# injectors.net
KiCad netlist of a schematic drawn in Altium Designer
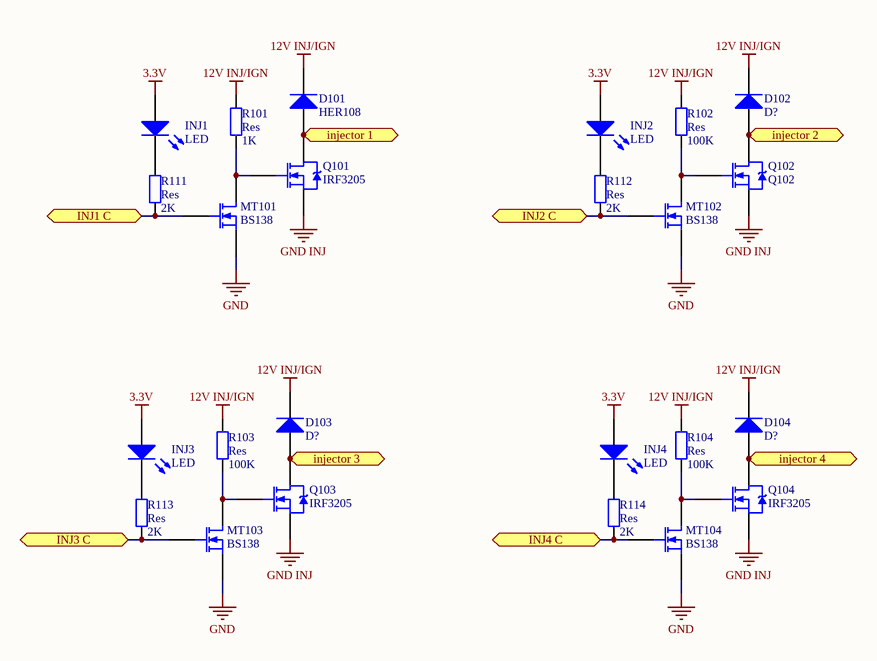
[diagram p0: injectors.SchDoc]

(export (version "E")
  (design (tool "Eeschema 10.0.6"))
  (components
    (comp (ref "D101") (value "HER108") (footprint "1N4007") (libsource (lib "ArduinoNano") (part "1N4007")))
    (comp (ref "D102") (value "D?") (footprint "1N4007") (libsource (lib "ArduinoNano") (part "1N4007")))
    (comp (ref "D103") (value "D?") (footprint "1N4007") (libsource (lib "ArduinoNano") (part "1N4007")))
    (comp (ref "D104") (value "D?") (footprint "1N4007") (libsource (lib "ArduinoNano") (part "1N4007")))
    (comp (ref "INJ1") (value "LED") (footprint "LED 3mm") (libsource (lib "ArduinoNano") (part "LED")))
    (comp (ref "INJ2") (value "LED") (footprint "LED 3mm") (libsource (lib "ArduinoNano") (part "LED")))
    (comp (ref "INJ3") (value "LED") (footprint "LED 3mm") (libsource (lib "ArduinoNano") (part "LED")))
    (comp (ref "INJ4") (value "LED") (footprint "LED 3mm") (libsource (lib "ArduinoNano") (part "LED")))
    (comp (ref "MT101") (value "BS138") (footprint "SOT23") (libsource (lib "ArduinoNano") (part "BS138")))
    (comp (ref "MT102") (value "BS138") (footprint "SOT23") (libsource (lib "ArduinoNano") (part "BS138")))
    (comp (ref "MT103") (value "BS138") (footprint "SOT23") (libsource (lib "ArduinoNano") (part "BS138")))
    (comp (ref "MT104") (value "BS138") (footprint "SOT23") (libsource (lib "ArduinoNano") (part "BS138")))
    (comp (ref "Q101")
      (value "IRF3205")
      (footprint "TO-220AB")
      (description "HEXFET Power MOSFET")
      (fields (field (name "PUBLISHER") "Altium Limited"))
      (libsource (lib "IR Discrete MOSFET - Power") (part "IRF3205"))
    )
    (comp (ref "Q102")
      (value "Q102")
      (footprint "TO-220AB")
      (description "HEXFET Power MOSFET")
      (fields (field (name "PUBLISHER") "Altium Limited"))
      (libsource (lib "IR Discrete MOSFET - Power") (part "IRF3205"))
    )
    (comp (ref "Q103")
      (value "IRF3205")
      (footprint "TO-220AB")
      (description "HEXFET Power MOSFET")
      (fields (field (name "PUBLISHER") "Altium Limited"))
      (libsource (lib "IR Discrete MOSFET - Power") (part "IRF3205"))
    )
    (comp (ref "Q104")
      (value "IRF3205")
      (footprint "TO-220AB")
      (description "HEXFET Power MOSFET")
      (fields (field (name "PUBLISHER") "Altium Limited"))
      (libsource (lib "IR Discrete MOSFET - Power") (part "IRF3205"))
    )
    (comp (ref "R101")
      (value "Res")
      (footprint "1206 footprint")
      (fields (field (name "ALTIUM_VALUE") "1K"))
      (libsource (lib "ArduinoNano") (part "Res"))
    )
    (comp (ref "R102")
      (value "Res")
      (footprint "1206 footprint")
      (fields (field (name "ALTIUM_VALUE") "100K"))
      (libsource (lib "ArduinoNano") (part "Res"))
    )
    (comp (ref "R103")
      (value "Res")
      (footprint "1206 footprint")
      (fields (field (name "ALTIUM_VALUE") "100K"))
      (libsource (lib "ArduinoNano") (part "Res"))
    )
    (comp (ref "R104")
      (value "Res")
      (footprint "1206 footprint")
      (fields (field (name "ALTIUM_VALUE") "100K"))
      (libsource (lib "ArduinoNano") (part "Res"))
    )
    (comp (ref "R111")
      (value "Res")
      (footprint "1206 footprint")
      (fields (field (name "ALTIUM_VALUE") "2K"))
      (libsource (lib "ArduinoNano") (part "Res"))
    )
    (comp (ref "R112")
      (value "Res")
      (footprint "1206 footprint")
      (fields (field (name "ALTIUM_VALUE") "2K"))
      (libsource (lib "ArduinoNano") (part "Res"))
    )
    (comp (ref "R113")
      (value "Res")
      (footprint "1206 footprint")
      (fields (field (name "ALTIUM_VALUE") "2K"))
      (libsource (lib "ArduinoNano") (part "Res"))
    )
    (comp (ref "R114")
      (value "Res")
      (footprint "1206 footprint")
      (fields (field (name "ALTIUM_VALUE") "2K"))
      (libsource (lib "ArduinoNano") (part "Res"))
    )
  )
  (nets
    (net (code "1") (name "/INJ1 C") (class "Default")
      (node (ref "MT101") (pin "1") (pinfunction "G_1") (pintype "passive"))
      (node (ref "R111") (pin "1") (pinfunction "1_1") (pintype "passive"))
    )
    (net (code "2") (name "/INJ2 C") (class "Default")
      (node (ref "MT102") (pin "1") (pinfunction "G_1") (pintype "passive"))
      (node (ref "R112") (pin "1") (pinfunction "1_1") (pintype "passive"))
    )
    (net (code "3") (name "/INJ3 C") (class "Default")
      (node (ref "MT103") (pin "1") (pinfunction "G_1") (pintype "passive"))
      (node (ref "R113") (pin "1") (pinfunction "1_1") (pintype "passive"))
    )
    (net (code "4") (name "/INJ4 C") (class "Default")
      (node (ref "MT104") (pin "1") (pinfunction "G_1") (pintype "passive"))
      (node (ref "R114") (pin "1") (pinfunction "1_1") (pintype "passive"))
    )
    (net (code "5") (name "/injector 1") (class "Default")
      (node (ref "D101") (pin "1") (pinfunction "A_1") (pintype "passive"))
      (node (ref "Q101") (pin "2") (pinfunction "D_2") (pintype "passive"))
    )
    (net (code "6") (name "/injector 2") (class "Default")
      (node (ref "D102") (pin "1") (pinfunction "A_1") (pintype "passive"))
      (node (ref "Q102") (pin "2") (pinfunction "D_2") (pintype "passive"))
    )
    (net (code "7") (name "/injector 3") (class "Default")
      (node (ref "D103") (pin "1") (pinfunction "A_1") (pintype "passive"))
      (node (ref "Q103") (pin "2") (pinfunction "D_2") (pintype "passive"))
    )
    (net (code "8") (name "/injector 4") (class "Default")
      (node (ref "D104") (pin "1") (pinfunction "A_1") (pintype "passive"))
      (node (ref "Q104") (pin "2") (pinfunction "D_2") (pintype "passive"))
    )
    (net (code "9") (name "3.3V") (class "Default")
      (node (ref "INJ1") (pin "1") (pinfunction "A_1") (pintype "passive"))
      (node (ref "INJ2") (pin "1") (pinfunction "A_1") (pintype "passive"))
      (node (ref "INJ3") (pin "1") (pinfunction "A_1") (pintype "passive"))
      (node (ref "INJ4") (pin "1") (pinfunction "A_1") (pintype "passive"))
    )
    (net (code "10") (name "12V INJ{slash}IGN") (class "Default")
      (node (ref "D101") (pin "2") (pinfunction "K_2") (pintype "passive"))
      (node (ref "D102") (pin "2") (pinfunction "K_2") (pintype "passive"))
      (node (ref "D103") (pin "2") (pinfunction "K_2") (pintype "passive"))
      (node (ref "D104") (pin "2") (pinfunction "K_2") (pintype "passive"))
      (node (ref "R101") (pin "2") (pinfunction "2_2") (pintype "passive"))
      (node (ref "R102") (pin "2") (pinfunction "2_2") (pintype "passive"))
      (node (ref "R103") (pin "2") (pinfunction "2_2") (pintype "passive"))
      (node (ref "R104") (pin "2") (pinfunction "2_2") (pintype "passive"))
    )
    (net (code "11") (name "GND") (class "Default")
      (node (ref "MT101") (pin "2") (pinfunction "S_2") (pintype "passive"))
      (node (ref "MT102") (pin "2") (pinfunction "S_2") (pintype "passive"))
      (node (ref "MT103") (pin "2") (pinfunction "S_2") (pintype "passive"))
      (node (ref "MT104") (pin "2") (pinfunction "S_2") (pintype "passive"))
    )
    (net (code "12") (name "GND INJ") (class "Default")
      (node (ref "Q101") (pin "3") (pinfunction "S_3") (pintype "passive"))
      (node (ref "Q102") (pin "3") (pinfunction "S_3") (pintype "passive"))
      (node (ref "Q103") (pin "3") (pinfunction "S_3") (pintype "passive"))
      (node (ref "Q104") (pin "3") (pinfunction "S_3") (pintype "passive"))
    )
    (net (code "13") (name "Net-(INJ1-K)") (class "Default")
      (node (ref "INJ1") (pin "2") (pinfunction "K_2") (pintype "passive"))
      (node (ref "R111") (pin "2") (pinfunction "2_2") (pintype "passive"))
    )
    (net (code "14") (name "Net-(INJ2-K)") (class "Default")
      (node (ref "INJ2") (pin "2") (pinfunction "K_2") (pintype "passive"))
      (node (ref "R112") (pin "2") (pinfunction "2_2") (pintype "passive"))
    )
    (net (code "15") (name "Net-(INJ3-K)") (class "Default")
      (node (ref "INJ3") (pin "2") (pinfunction "K_2") (pintype "passive"))
      (node (ref "R113") (pin "2") (pinfunction "2_2") (pintype "passive"))
    )
    (net (code "16") (name "Net-(INJ4-K)") (class "Default")
      (node (ref "INJ4") (pin "2") (pinfunction "K_2") (pintype "passive"))
      (node (ref "R114") (pin "2") (pinfunction "2_2") (pintype "passive"))
    )
    (net (code "17") (name "Net-(MT101-D)") (class "Default")
      (node (ref "MT101") (pin "3") (pinfunction "D_3") (pintype "passive"))
      (node (ref "Q101") (pin "1") (pinfunction "G_1") (pintype "passive"))
      (node (ref "R101") (pin "1") (pinfunction "1_1") (pintype "passive"))
    )
    (net (code "18") (name "Net-(MT102-D)") (class "Default")
      (node (ref "MT102") (pin "3") (pinfunction "D_3") (pintype "passive"))
      (node (ref "Q102") (pin "1") (pinfunction "G_1") (pintype "passive"))
      (node (ref "R102") (pin "1") (pinfunction "1_1") (pintype "passive"))
    )
    (net (code "19") (name "Net-(MT103-D)") (class "Default")
      (node (ref "MT103") (pin "3") (pinfunction "D_3") (pintype "passive"))
      (node (ref "Q103") (pin "1") (pinfunction "G_1") (pintype "passive"))
      (node (ref "R103") (pin "1") (pinfunction "1_1") (pintype "passive"))
    )
    (net (code "20") (name "Net-(MT104-D)") (class "Default")
      (node (ref "MT104") (pin "3") (pinfunction "D_3") (pintype "passive"))
      (node (ref "Q104") (pin "1") (pinfunction "G_1") (pintype "passive"))
      (node (ref "R104") (pin "1") (pinfunction "1_1") (pintype "passive"))
    )
  )
)
